# 0251.net
KiCad netlist of a schematic drawn in EAGLE
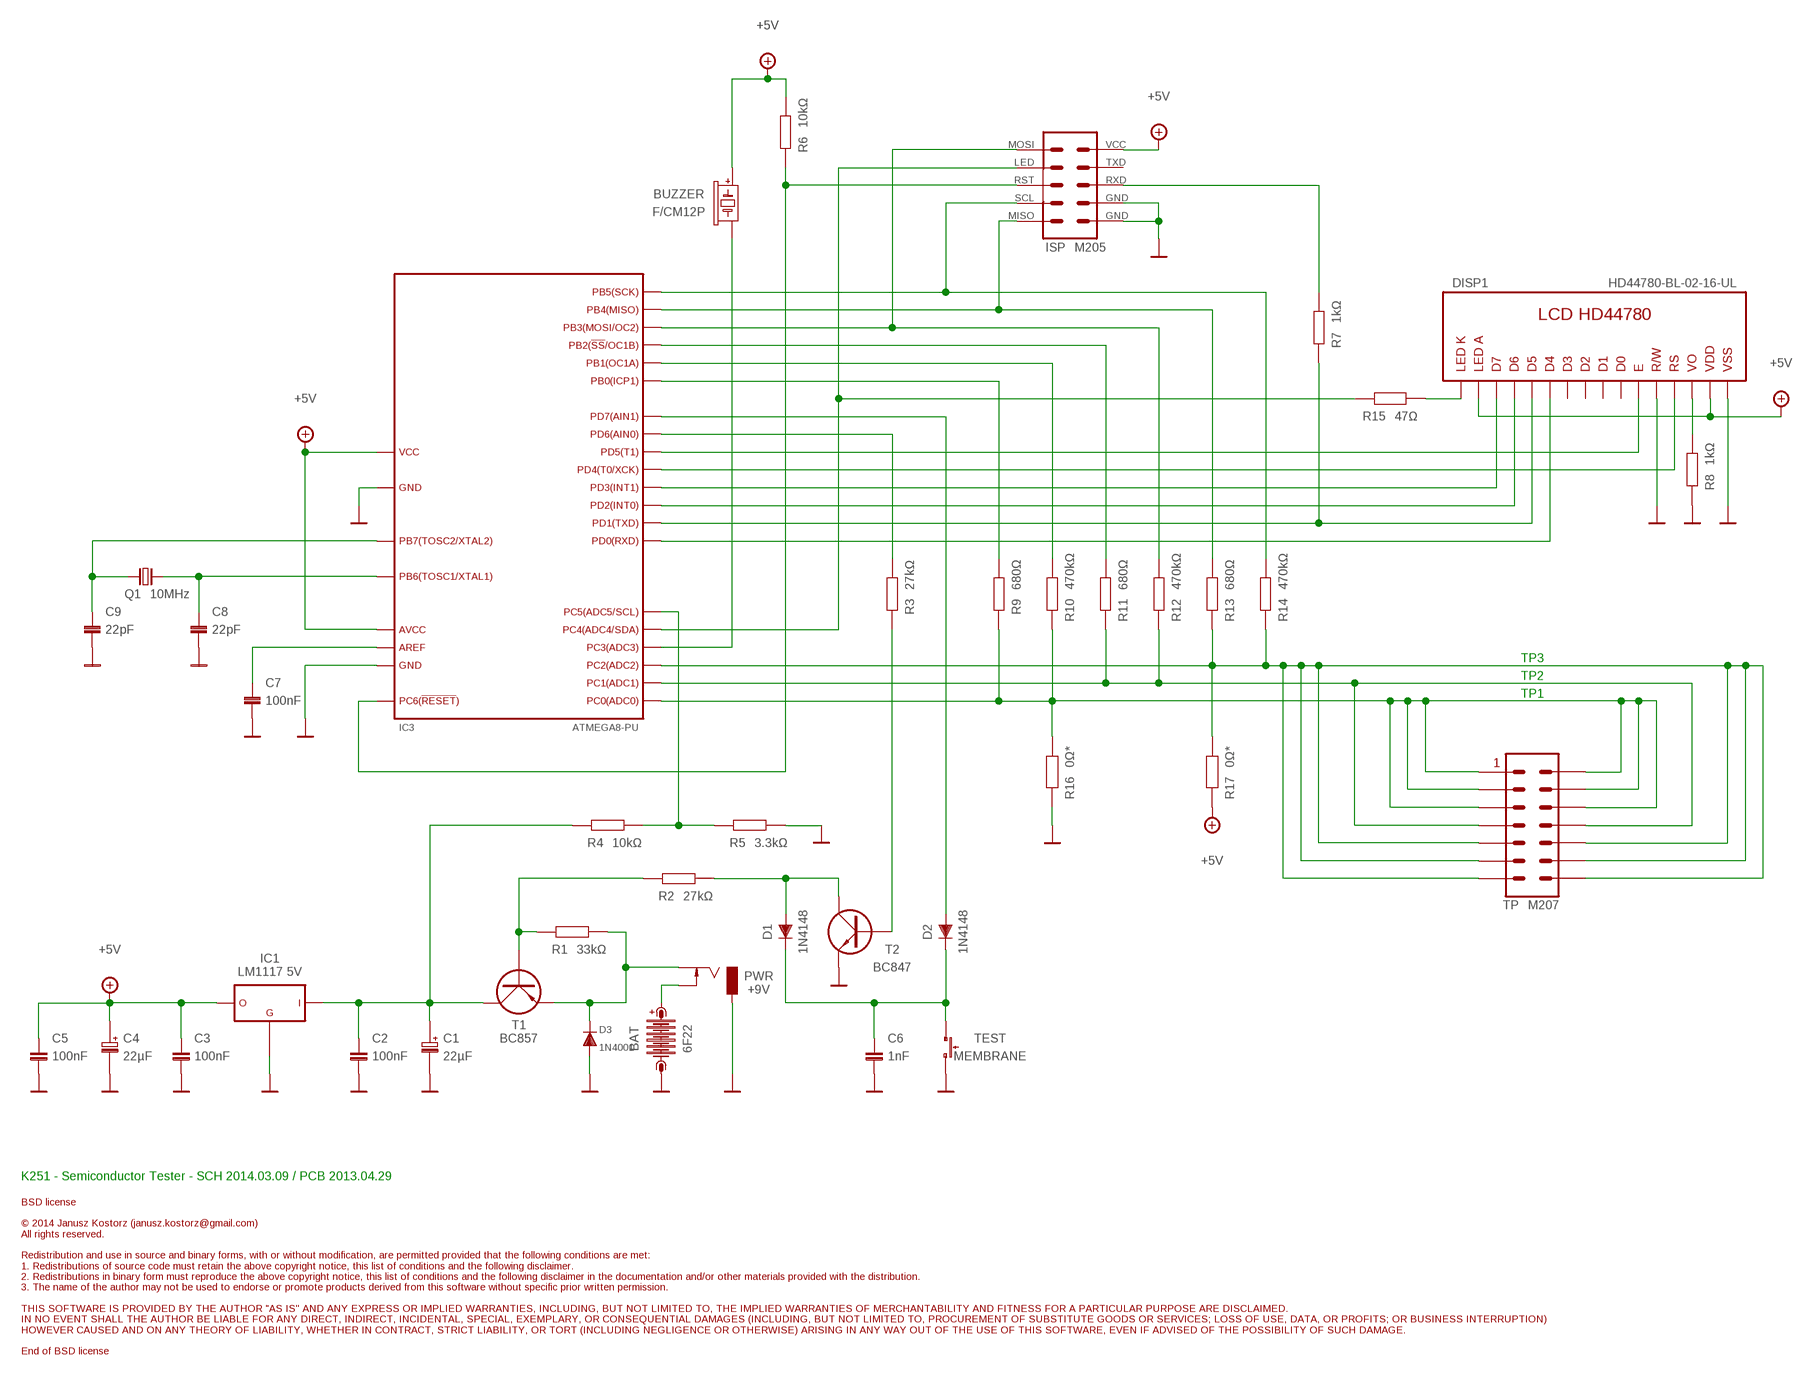
[diagram p0: schematic, sheet 1]

(export (version "E")
  (design (tool "Eeschema 10.0.6"))
  (components
    (comp (ref "BAT")
      (value "6F22")
      (footprint "eagle-import:AB9V")
      (libsource (lib "eagle-import") (part "AB9V"))
    )
    (comp (ref "BUZZER")
      (value "F/CM12P")
      (footprint "eagle-import:BUZZER_F_CM12P")
      (libsource (lib "eagle-import") (part "BUZZER_F/CM12P"))
    )
    (comp (ref "C1")
      (value "22µF")
      (footprint "eagle-import:E-050-110-020-05")
      (fields (field (name "VOLTAGE") "10V"))
      (libsource (lib "eagle-import") (part "FM1A101"))
    )
    (comp (ref "C2")
      (value "100nF")
      (footprint "eagle-import:C1206")
      (libsource (lib "eagle-import") (part "CC1206"))
    )
    (comp (ref "C3")
      (value "100nF")
      (footprint "eagle-import:C1206")
      (libsource (lib "eagle-import") (part "CC1206"))
    )
    (comp (ref "C4")
      (value "22µF")
      (footprint "eagle-import:E-050-110-020-05")
      (fields (field (name "VOLTAGE") "10V"))
      (libsource (lib "eagle-import") (part "FM1A101"))
    )
    (comp (ref "C5")
      (value "100nF")
      (footprint "eagle-import:C1206")
      (libsource (lib "eagle-import") (part "CC1206"))
    )
    (comp (ref "C6")
      (value "1nF")
      (footprint "eagle-import:C1206")
      (libsource (lib "eagle-import") (part "CC1206"))
    )
    (comp (ref "C7")
      (value "100nF")
      (footprint "eagle-import:C1206")
      (libsource (lib "eagle-import") (part "CC1206"))
    )
    (comp (ref "C8")
      (value "22pF")
      (footprint "eagle-import:C1206")
      (libsource (lib "eagle-import") (part "CC1206"))
    )
    (comp (ref "C9")
      (value "22pF")
      (footprint "eagle-import:C1206")
      (libsource (lib "eagle-import") (part "CC1206"))
    )
    (comp (ref "D1")
      (value "1N4148")
      (footprint "eagle-import:DO35-10")
      (libsource (lib "eagle-import") (part "1N4148DO35-10"))
    )
    (comp (ref "D2")
      (value "1N4148")
      (footprint "eagle-import:DO35-10")
      (libsource (lib "eagle-import") (part "1N4148DO35-10"))
    )
    (comp (ref "D3")
      (value "1N4001")
      (footprint "eagle-import:DO41-10")
      (libsource (lib "eagle-import") (part "1N4004"))
    )
    (comp (ref "DISP1")
      (value "HD44780-BL-02-16-UL")
      (footprint "eagle-import:02-16-UL-BL")
      (libsource (lib "eagle-import") (part "HD44780-BL-02-16-UL"))
    )
    (comp (ref "IC1")
      (value "LM1117 5V")
      (footprint "eagle-import:TO252")
      (libsource (lib "eagle-import") (part "LM1117DTX-5.0"))
    )
    (comp (ref "IC3")
      (value "ATMEGA8-PU")
      (footprint "eagle-import:DIP254P800X550-28B")
      (libsource (lib "eagle-import") (part "ATMEGA8-PU"))
    )
    (comp (ref "ISP")
      (value "M205")
      (footprint "eagle-import:MM-10-H")
      (libsource (lib "eagle-import") (part "ATMEL-ISP-10-UART-H"))
    )
    (comp (ref "PWR")
      (value "+9V")
      (footprint "eagle-import:DCJ0303")
      (libsource (lib "eagle-import") (part "DCJ0303"))
    )
    (comp (ref "Q1")
      (value "10MHz")
      (footprint "eagle-import:HC49_S")
      (libsource (lib "eagle-import") (part "CRYSTALHC49S"))
    )
    (comp (ref "R1")
      (value "33kΩ")
      (footprint "eagle-import:R1206")
      (libsource (lib "eagle-import") (part "RR1206"))
    )
    (comp (ref "R2")
      (value "27kΩ")
      (footprint "eagle-import:R1206")
      (libsource (lib "eagle-import") (part "RR1206"))
    )
    (comp (ref "R3")
      (value "27kΩ")
      (footprint "eagle-import:R1206")
      (libsource (lib "eagle-import") (part "RR1206"))
    )
    (comp (ref "R4")
      (value "10kΩ")
      (footprint "eagle-import:R1206")
      (libsource (lib "eagle-import") (part "RR1206"))
    )
    (comp (ref "R5")
      (value "3.3kΩ")
      (footprint "eagle-import:R1206")
      (libsource (lib "eagle-import") (part "RR1206"))
    )
    (comp (ref "R6")
      (value "10kΩ")
      (footprint "eagle-import:R1206")
      (libsource (lib "eagle-import") (part "RR1206"))
    )
    (comp (ref "R7")
      (value "1kΩ")
      (footprint "eagle-import:R1206")
      (libsource (lib "eagle-import") (part "RR1206"))
    )
    (comp (ref "R8")
      (value "1kΩ")
      (footprint "eagle-import:R1206")
      (libsource (lib "eagle-import") (part "RR1206"))
    )
    (comp (ref "R9")
      (value "680Ω")
      (footprint "eagle-import:0207_12")
      (libsource (lib "eagle-import") (part "R0207/12"))
    )
    (comp (ref "R10")
      (value "470kΩ")
      (footprint "eagle-import:0207_12")
      (libsource (lib "eagle-import") (part "R0207/12"))
    )
    (comp (ref "R11")
      (value "680Ω")
      (footprint "eagle-import:0207_12")
      (libsource (lib "eagle-import") (part "R0207/12"))
    )
    (comp (ref "R12")
      (value "470kΩ")
      (footprint "eagle-import:0207_12")
      (libsource (lib "eagle-import") (part "R0207/12"))
    )
    (comp (ref "R13")
      (value "680Ω")
      (footprint "eagle-import:0207_12")
      (libsource (lib "eagle-import") (part "R0207/12"))
    )
    (comp (ref "R14")
      (value "470kΩ")
      (footprint "eagle-import:0207_12")
      (libsource (lib "eagle-import") (part "R0207/12"))
    )
    (comp (ref "R15")
      (value "47Ω")
      (footprint "eagle-import:R1206")
      (libsource (lib "eagle-import") (part "RR1206"))
    )
    (comp (ref "R16")
      (value "0Ω*")
      (footprint "eagle-import:R1206")
      (libsource (lib "eagle-import") (part "RR1206"))
    )
    (comp (ref "R17")
      (value "0Ω*")
      (footprint "eagle-import:R1206")
      (libsource (lib "eagle-import") (part "RR1206"))
    )
    (comp (ref "T1")
      (value "BC857")
      (footprint "eagle-import:SOT23-BEC")
      (libsource (lib "eagle-import") (part "BC857SMDA"))
    )
    (comp (ref "T2")
      (value "BC847")
      (footprint "eagle-import:SOT23-BEC")
      (libsource (lib "eagle-import") (part "BC847SMDA"))
    )
    (comp (ref "TEST")
      (value "MEMBRANE")
      (footprint "eagle-import:B3F-10XX-M")
      (fields (field (name "MPN") "B3F-1000"))
      (libsource (lib "eagle-import") (part "10-XX"))
    )
    (comp (ref "TP")
      (value "M207")
      (footprint "eagle-import:2-7")
      (libsource (lib "eagle-import") (part "2-7"))
    )
  )
  (nets
    (net (code "1") (name "+5V") (class "Default")
      (node (ref "BUZZER") (pin "+") (pinfunction "1_+") (pintype "passive"))
      (node (ref "C3") (pin "2") (pinfunction "2_2") (pintype "passive"))
      (node (ref "C4") (pin "+") (pinfunction "+_+") (pintype "passive"))
      (node (ref "C5") (pin "2") (pinfunction "2_2") (pintype "passive"))
      (node (ref "DISP1") (pin "15") (pinfunction "A_15") (pintype "power_in"))
      (node (ref "DISP1") (pin "2") (pinfunction "VDD_2") (pintype "power_in"))
      (node (ref "IC1") (pin "2") (pinfunction "OUT_2") (pintype "passive"))
      (node (ref "IC3") (pin "20") (pinfunction "AVCC_20") (pintype "power_in"))
      (node (ref "IC3") (pin "7") (pinfunction "VCC_7") (pintype "power_in"))
      (node (ref "ISP") (pin "P$2") (pinfunction "VCC_P$2") (pintype "power_in"))
      (node (ref "R17") (pin "2") (pinfunction "2_2") (pintype "passive"))
      (node (ref "R6") (pin "2") (pinfunction "2_2") (pintype "passive"))
    )
    (net (code "2") (name "GND") (class "Default")
      (node (ref "BAT") (pin "-") (pinfunction "-_-") (pintype "passive"))
      (node (ref "C1") (pin "-") (pinfunction "-_-") (pintype "passive"))
      (node (ref "C2") (pin "1") (pinfunction "1_1") (pintype "passive"))
      (node (ref "C3") (pin "1") (pinfunction "1_1") (pintype "passive"))
      (node (ref "C4") (pin "-") (pinfunction "-_-") (pintype "passive"))
      (node (ref "C5") (pin "1") (pinfunction "1_1") (pintype "passive"))
      (node (ref "C6") (pin "1") (pinfunction "1_1") (pintype "passive"))
      (node (ref "C7") (pin "1") (pinfunction "1_1") (pintype "passive"))
      (node (ref "C8") (pin "1") (pinfunction "1_1") (pintype "passive"))
      (node (ref "C9") (pin "1") (pinfunction "1_1") (pintype "passive"))
      (node (ref "D3") (pin "A") (pinfunction "A_A") (pintype "passive"))
      (node (ref "DISP1") (pin "1") (pinfunction "VSS_1") (pintype "power_in"))
      (node (ref "DISP1") (pin "5") (pinfunction "R/W_5") (pintype "input"))
      (node (ref "IC1") (pin "1") (pinfunction "GND_1") (pintype "passive"))
      (node (ref "IC3") (pin "22") (pinfunction "GND_22") (pintype "power_in"))
      (node (ref "IC3") (pin "8") (pinfunction "GND_8") (pintype "power_in"))
      (node (ref "ISP") (pin "P$10") (pinfunction "GND_P$10") (pintype "power_in"))
      (node (ref "ISP") (pin "P$8") (pinfunction "GND_P$8") (pintype "power_in"))
      (node (ref "PWR") (pin "1") (pinfunction "1_1") (pintype "passive"))
      (node (ref "R16") (pin "2") (pinfunction "2_2") (pintype "passive"))
      (node (ref "R5") (pin "1") (pinfunction "1_1") (pintype "passive"))
      (node (ref "R8") (pin "1") (pinfunction "1_1") (pintype "passive"))
      (node (ref "T2") (pin "E") (pinfunction "E_E") (pintype "passive"))
      (node (ref "TEST") (pin "1") (pinfunction "S_1") (pintype "passive"))
    )
    (net (code "3") (name "Net-(BAT-Pad+)") (class "Default")
      (node (ref "BAT") (pin "+") (pinfunction "+_+") (pintype "passive"))
      (node (ref "PWR") (pin "2") (pinfunction "2_2") (pintype "passive"))
    )
    (net (code "4") (name "Net-(BUZZER-2)") (class "Default")
      (node (ref "BUZZER") (pin "-") (pinfunction "2_-") (pintype "passive"))
      (node (ref "IC3") (pin "26") (pinfunction "PC3_26") (pintype "bidirectional"))
    )
    (net (code "5") (name "Net-(D1-PadA)") (class "Default")
      (node (ref "D1") (pin "A") (pinfunction "A_A") (pintype "passive"))
      (node (ref "R2") (pin "1") (pinfunction "1_1") (pintype "passive"))
      (node (ref "T2") (pin "C") (pinfunction "C_C") (pintype "passive"))
    )
    (net (code "6") (name "Net-(D3-PadC)") (class "Default")
      (node (ref "D3") (pin "C") (pinfunction "C_C") (pintype "passive"))
      (node (ref "PWR") (pin "3") (pinfunction "3_3") (pintype "passive"))
      (node (ref "R1") (pin "2") (pinfunction "2_2") (pintype "passive"))
      (node (ref "T1") (pin "E") (pinfunction "E_E") (pintype "passive"))
    )
    (net (code "7") (name "Net-(DISP1-DB4)") (class "Default")
      (node (ref "DISP1") (pin "11") (pinfunction "DB4_11") (pintype "bidirectional"))
      (node (ref "IC3") (pin "2") (pinfunction "PD0_2") (pintype "bidirectional"))
    )
    (net (code "8") (name "Net-(DISP1-DB5)") (class "Default")
      (node (ref "DISP1") (pin "12") (pinfunction "DB5_12") (pintype "bidirectional"))
      (node (ref "IC3") (pin "3") (pinfunction "PD1_3") (pintype "bidirectional"))
      (node (ref "R7") (pin "2") (pinfunction "2_2") (pintype "passive"))
    )
    (net (code "9") (name "Net-(DISP1-DB6)") (class "Default")
      (node (ref "DISP1") (pin "13") (pinfunction "DB6_13") (pintype "bidirectional"))
      (node (ref "IC3") (pin "4") (pinfunction "PD2_4") (pintype "bidirectional"))
    )
    (net (code "10") (name "Net-(DISP1-DB7)") (class "Default")
      (node (ref "DISP1") (pin "14") (pinfunction "DB7_14") (pintype "bidirectional"))
      (node (ref "IC3") (pin "5") (pinfunction "PD3_5") (pintype "bidirectional"))
    )
    (net (code "11") (name "Net-(DISP1-E)") (class "Default")
      (node (ref "DISP1") (pin "6") (pinfunction "E_6") (pintype "input"))
      (node (ref "IC3") (pin "11") (pinfunction "PD5_11") (pintype "bidirectional"))
    )
    (net (code "12") (name "Net-(DISP1-K)") (class "Default")
      (node (ref "DISP1") (pin "16") (pinfunction "K_16") (pintype "power_in"))
      (node (ref "R15") (pin "1") (pinfunction "1_1") (pintype "passive"))
    )
    (net (code "13") (name "Net-(DISP1-RS)") (class "Default")
      (node (ref "DISP1") (pin "4") (pinfunction "RS_4") (pintype "input"))
      (node (ref "IC3") (pin "6") (pinfunction "PD4_6") (pintype "bidirectional"))
    )
    (net (code "14") (name "Net-(DISP1-VO)") (class "Default")
      (node (ref "DISP1") (pin "3") (pinfunction "VO_3") (pintype "bidirectional"))
      (node (ref "R8") (pin "2") (pinfunction "2_2") (pintype "passive"))
    )
    (net (code "15") (name "Net-(IC1-IN)") (class "Default")
      (node (ref "C1") (pin "+") (pinfunction "+_+") (pintype "passive"))
      (node (ref "C2") (pin "2") (pinfunction "2_2") (pintype "passive"))
      (node (ref "IC1") (pin "3") (pinfunction "IN_3") (pintype "input"))
      (node (ref "R4") (pin "2") (pinfunction "2_2") (pintype "passive"))
      (node (ref "T1") (pin "C") (pinfunction "C_C") (pintype "passive"))
    )
    (net (code "16") (name "Net-(IC3-AREF)") (class "Default")
      (node (ref "C7") (pin "2") (pinfunction "2_2") (pintype "passive"))
      (node (ref "IC3") (pin "21") (pinfunction "AREF_21") (pintype "passive"))
    )
    (net (code "17") (name "Net-(IC3-PB0)") (class "Default")
      (node (ref "IC3") (pin "14") (pinfunction "PB0_14") (pintype "bidirectional"))
      (node (ref "R9") (pin "1") (pinfunction "1_1") (pintype "passive"))
    )
    (net (code "18") (name "Net-(IC3-PB1)") (class "Default")
      (node (ref "IC3") (pin "15") (pinfunction "PB1_15") (pintype "bidirectional"))
      (node (ref "R10") (pin "1") (pinfunction "1_1") (pintype "passive"))
    )
    (net (code "19") (name "Net-(IC3-PB2)") (class "Default")
      (node (ref "IC3") (pin "16") (pinfunction "PB2_16") (pintype "bidirectional"))
      (node (ref "R11") (pin "1") (pinfunction "1_1") (pintype "passive"))
    )
    (net (code "20") (name "Net-(IC3-PB3)") (class "Default")
      (node (ref "IC3") (pin "17") (pinfunction "PB3_17") (pintype "bidirectional"))
      (node (ref "ISP") (pin "P$1") (pinfunction "MOSI_P$1") (pintype "bidirectional"))
      (node (ref "R12") (pin "1") (pinfunction "1_1") (pintype "passive"))
    )
    (net (code "21") (name "Net-(IC3-PB4)") (class "Default")
      (node (ref "IC3") (pin "18") (pinfunction "PB4_18") (pintype "bidirectional"))
      (node (ref "ISP") (pin "P$9") (pinfunction "MISO_P$9") (pintype "bidirectional"))
      (node (ref "R13") (pin "1") (pinfunction "1_1") (pintype "passive"))
    )
    (net (code "22") (name "Net-(IC3-PB5)") (class "Default")
      (node (ref "IC3") (pin "19") (pinfunction "PB5_19") (pintype "bidirectional"))
      (node (ref "ISP") (pin "P$7") (pinfunction "SCL_P$7") (pintype "bidirectional"))
      (node (ref "R14") (pin "1") (pinfunction "1_1") (pintype "passive"))
    )
    (net (code "23") (name "Net-(IC3-PB6)") (class "Default")
      (node (ref "C8") (pin "2") (pinfunction "2_2") (pintype "passive"))
      (node (ref "IC3") (pin "9") (pinfunction "PB6_9") (pintype "bidirectional"))
      (node (ref "Q1") (pin "2") (pinfunction "2_2") (pintype "passive"))
    )
    (net (code "24") (name "Net-(IC3-PB7)") (class "Default")
      (node (ref "C9") (pin "2") (pinfunction "2_2") (pintype "passive"))
      (node (ref "IC3") (pin "10") (pinfunction "PB7_10") (pintype "bidirectional"))
      (node (ref "Q1") (pin "1") (pinfunction "1_1") (pintype "passive"))
    )
    (net (code "25") (name "Net-(IC3-PC0)") (class "Default")
      (node (ref "IC3") (pin "23") (pinfunction "PC0_23") (pintype "bidirectional"))
      (node (ref "R10") (pin "2") (pinfunction "2_2") (pintype "passive"))
      (node (ref "R16") (pin "1") (pinfunction "1_1") (pintype "passive"))
      (node (ref "R9") (pin "2") (pinfunction "2_2") (pintype "passive"))
      (node (ref "TP") (pin "1") (pinfunction "1_1") (pintype "passive"))
      (node (ref "TP") (pin "2") (pinfunction "2_2") (pintype "passive"))
      (node (ref "TP") (pin "3") (pinfunction "3_3") (pintype "passive"))
      (node (ref "TP") (pin "4") (pinfunction "4_4") (pintype "passive"))
      (node (ref "TP") (pin "5") (pinfunction "5_5") (pintype "passive"))
      (node (ref "TP") (pin "6") (pinfunction "6_6") (pintype "passive"))
    )
    (net (code "26") (name "Net-(IC3-PC1)") (class "Default")
      (node (ref "IC3") (pin "24") (pinfunction "PC1_24") (pintype "bidirectional"))
      (node (ref "R11") (pin "2") (pinfunction "2_2") (pintype "passive"))
      (node (ref "R12") (pin "2") (pinfunction "2_2") (pintype "passive"))
      (node (ref "TP") (pin "7") (pinfunction "7_7") (pintype "passive"))
      (node (ref "TP") (pin "8") (pinfunction "8_8") (pintype "passive"))
    )
    (net (code "27") (name "Net-(IC3-PC2)") (class "Default")
      (node (ref "IC3") (pin "25") (pinfunction "PC2_25") (pintype "bidirectional"))
      (node (ref "R13") (pin "2") (pinfunction "2_2") (pintype "passive"))
      (node (ref "R14") (pin "2") (pinfunction "2_2") (pintype "passive"))
      (node (ref "R17") (pin "1") (pinfunction "1_1") (pintype "passive"))
      (node (ref "TP") (pin "10") (pinfunction "10_10") (pintype "passive"))
      (node (ref "TP") (pin "11") (pinfunction "11_11") (pintype "passive"))
      (node (ref "TP") (pin "12") (pinfunction "12_12") (pintype "passive"))
      (node (ref "TP") (pin "13") (pinfunction "13_13") (pintype "passive"))
      (node (ref "TP") (pin "14") (pinfunction "14_14") (pintype "passive"))
      (node (ref "TP") (pin "9") (pinfunction "9_9") (pintype "passive"))
    )
    (net (code "28") (name "Net-(IC3-PC4)") (class "Default")
      (node (ref "IC3") (pin "27") (pinfunction "PC4_27") (pintype "bidirectional"))
      (node (ref "ISP") (pin "P$3") (pinfunction "LED_P$3") (pintype "bidirectional"))
      (node (ref "R15") (pin "2") (pinfunction "2_2") (pintype "passive"))
    )
    (net (code "29") (name "Net-(IC3-PC5)") (class "Default")
      (node (ref "IC3") (pin "28") (pinfunction "PC5_28") (pintype "bidirectional"))
      (node (ref "R4") (pin "1") (pinfunction "1_1") (pintype "passive"))
      (node (ref "R5") (pin "2") (pinfunction "2_2") (pintype "passive"))
    )
    (net (code "30") (name "Net-(IC3-PC6)") (class "Default")
      (node (ref "IC3") (pin "1") (pinfunction "PC6_1") (pintype "bidirectional"))
      (node (ref "ISP") (pin "P$5") (pinfunction "RST_P$5") (pintype "bidirectional"))
      (node (ref "R6") (pin "1") (pinfunction "1_1") (pintype "passive"))
    )
    (net (code "31") (name "Net-(IC3-PD6)") (class "Default")
      (node (ref "IC3") (pin "12") (pinfunction "PD6_12") (pintype "bidirectional"))
      (node (ref "R3") (pin "2") (pinfunction "2_2") (pintype "passive"))
    )
    (net (code "32") (name "Net-(IC3-PD7)") (class "Default")
      (node (ref "D2") (pin "A") (pinfunction "A_A") (pintype "passive"))
      (node (ref "IC3") (pin "13") (pinfunction "PD7_13") (pintype "bidirectional"))
    )
    (net (code "33") (name "Net-(ISP-RXD)") (class "Default")
      (node (ref "ISP") (pin "P$6") (pinfunction "RXD_P$6") (pintype "bidirectional"))
      (node (ref "R7") (pin "1") (pinfunction "1_1") (pintype "passive"))
    )
    (net (code "34") (name "Net-(R1-Pad1)") (class "Default")
      (node (ref "R1") (pin "1") (pinfunction "1_1") (pintype "passive"))
      (node (ref "R2") (pin "2") (pinfunction "2_2") (pintype "passive"))
      (node (ref "T1") (pin "B") (pinfunction "B_B") (pintype "passive"))
    )
    (net (code "35") (name "Net-(R3-Pad1)") (class "Default")
      (node (ref "R3") (pin "1") (pinfunction "1_1") (pintype "passive"))
      (node (ref "T2") (pin "B") (pinfunction "B_B") (pintype "passive"))
    )
    (net (code "36") (name "Net-(TEST-P)") (class "Default")
      (node (ref "C6") (pin "2") (pinfunction "2_2") (pintype "passive"))
      (node (ref "D1") (pin "C") (pinfunction "C_C") (pintype "passive"))
      (node (ref "D2") (pin "C") (pinfunction "C_C") (pintype "passive"))
      (node (ref "TEST") (pin "3") (pinfunction "P_3") (pintype "passive"))
    )
    (net (code "37") (name "unconnected-(DISP1-DB0-Pad7)") (class "Default")
      (node (ref "DISP1") (pin "7") (pinfunction "DB0_7") (pintype "bidirectional"))
    )
    (net (code "38") (name "unconnected-(DISP1-DB1-Pad8)") (class "Default")
      (node (ref "DISP1") (pin "8") (pinfunction "DB1_8") (pintype "bidirectional"))
    )
    (net (code "39") (name "unconnected-(DISP1-DB2-Pad9)") (class "Default")
      (node (ref "DISP1") (pin "9") (pinfunction "DB2_9") (pintype "bidirectional"))
    )
    (net (code "40") (name "unconnected-(DISP1-DB3-Pad10)") (class "Default")
      (node (ref "DISP1") (pin "10") (pinfunction "DB3_10") (pintype "bidirectional"))
    )
    (net (code "41") (name "unconnected-(ISP-TXD-PadP$4)") (class "Default")
      (node (ref "ISP") (pin "P$4") (pinfunction "TXD_P$4") (pintype "bidirectional"))
    )
  )
)
